# NFC_BusinessCard.net
KiCad netlist of a schematic drawn in EAGLE
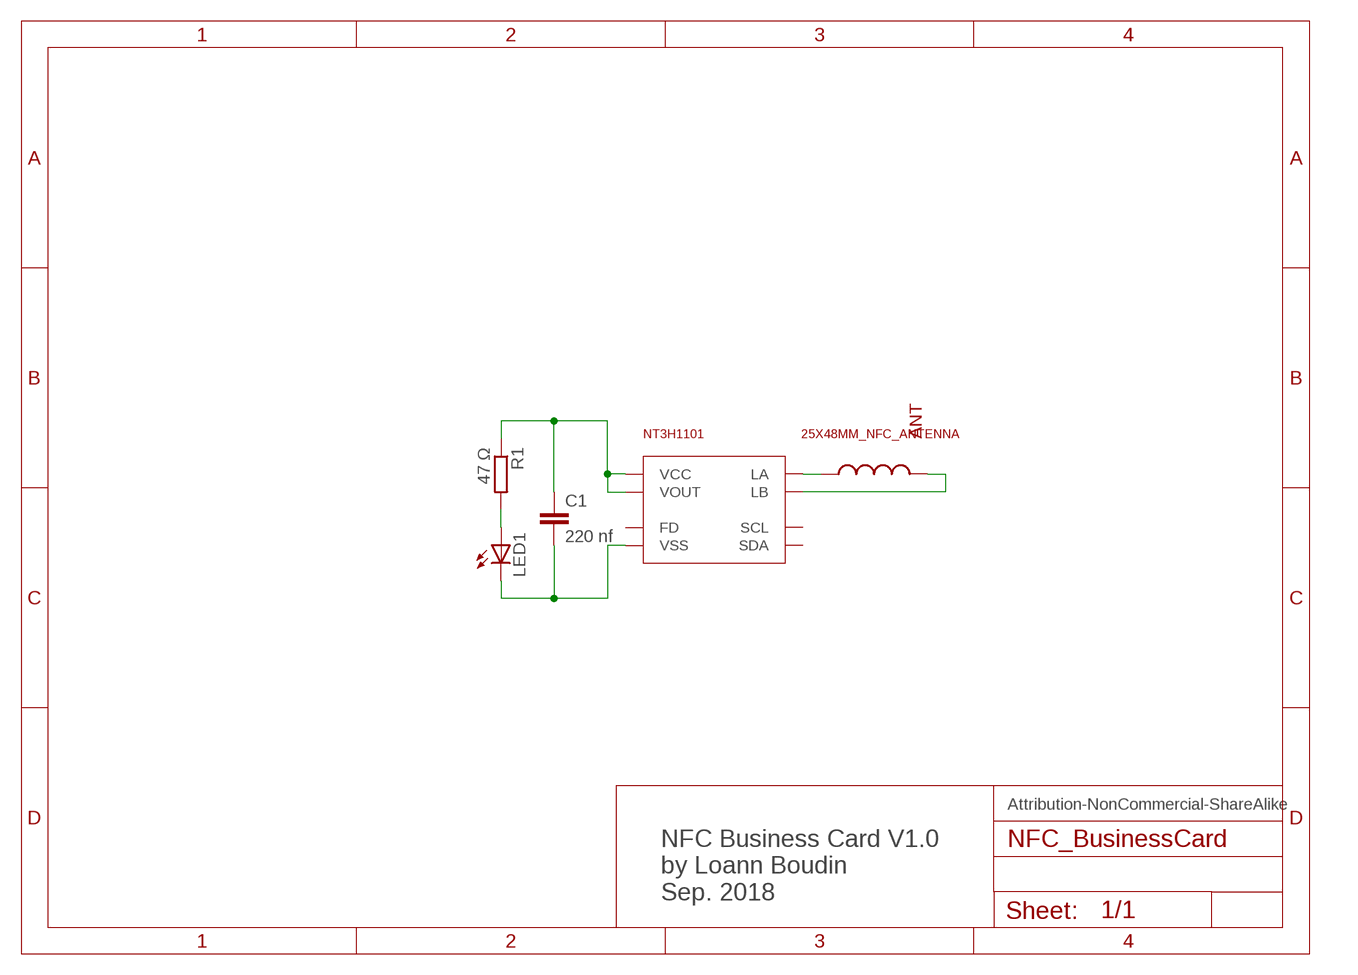
[diagram p0: schematic, sheet 1]

(export (version "E")
  (design (tool "Eeschema 10.0.6"))
  (components
    (comp (ref "ANT")
      (value "25X48MM_NFC_ANTENNA")
      (footprint "eagle-import:25X48MM_NFC")
      (libsource (lib "eagle-import") (part "25X48MM_NFC_ANTENNA"))
    )
    (comp (ref "C1")
      (value "220 nf")
      (footprint "eagle-import:C0603")
      (libsource (lib "eagle-import") (part "C-EUC0603"))
    )
    (comp (ref "LED1")
      (value "LEDSML0805")
      (footprint "eagle-import:SML0805")
      (libsource (lib "eagle-import") (part "LEDSML0805"))
    )
    (comp (ref "NT3H1101")
      (value "NT3H")
      (footprint "eagle-import:XQFN8")
      (libsource (lib "eagle-import") (part "NT3H"))
    )
    (comp (ref "R1")
      (value "47 Ω")
      (footprint "eagle-import:R0603")
      (libsource (lib "eagle-import") (part "R-EU_R0603"))
    )
  )
  (nets
    (net (code "1") (name "Net-(ANT-PadP$1)") (class "Default")
      (node (ref "ANT") (pin "P$1") (pinfunction "P$1_P$1") (pintype "bidirectional"))
      (node (ref "NT3H1101") (pin "LB") (pinfunction "LB_LB") (pintype "bidirectional"))
    )
    (net (code "2") (name "Net-(ANT-PadP$2)") (class "Default")
      (node (ref "ANT") (pin "P$2") (pinfunction "P$2_P$2") (pintype "bidirectional"))
      (node (ref "NT3H1101") (pin "LA") (pinfunction "LA_LA") (pintype "bidirectional"))
    )
    (net (code "3") (name "Net-(C1-Pad1)") (class "Default")
      (node (ref "C1") (pin "1") (pinfunction "1_1") (pintype "passive"))
      (node (ref "NT3H1101") (pin "VCC") (pinfunction "VCC_VCC") (pintype "bidirectional"))
      (node (ref "NT3H1101") (pin "VOUT") (pinfunction "VOUT_VOUT") (pintype "bidirectional"))
      (node (ref "R1") (pin "1") (pinfunction "1_1") (pintype "passive"))
    )
    (net (code "4") (name "Net-(C1-Pad2)") (class "Default")
      (node (ref "C1") (pin "2") (pinfunction "2_2") (pintype "passive"))
      (node (ref "LED1") (pin "C") (pinfunction "C_C") (pintype "passive"))
      (node (ref "NT3H1101") (pin "VSS") (pinfunction "VSS_VSS") (pintype "bidirectional"))
    )
    (net (code "5") (name "Net-(LED1-PadA)") (class "Default")
      (node (ref "LED1") (pin "A") (pinfunction "A_A") (pintype "passive"))
      (node (ref "R1") (pin "2") (pinfunction "2_2") (pintype "passive"))
    )
    (net (code "6") (name "unconnected-(NT3H1101-PadFD)") (class "Default")
      (node (ref "NT3H1101") (pin "FD") (pinfunction "FD_FD") (pintype "bidirectional"))
    )
    (net (code "7") (name "unconnected-(NT3H1101-PadSCL)") (class "Default")
      (node (ref "NT3H1101") (pin "SCL") (pinfunction "SCL_SCL") (pintype "bidirectional"))
    )
    (net (code "8") (name "unconnected-(NT3H1101-PadSDA)") (class "Default")
      (node (ref "NT3H1101") (pin "SDA") (pinfunction "SDA_SDA") (pintype "bidirectional"))
    )
  )
)
